# hothouse-no-branding.net
KiCad netlist of a schematic drawn in EAGLE
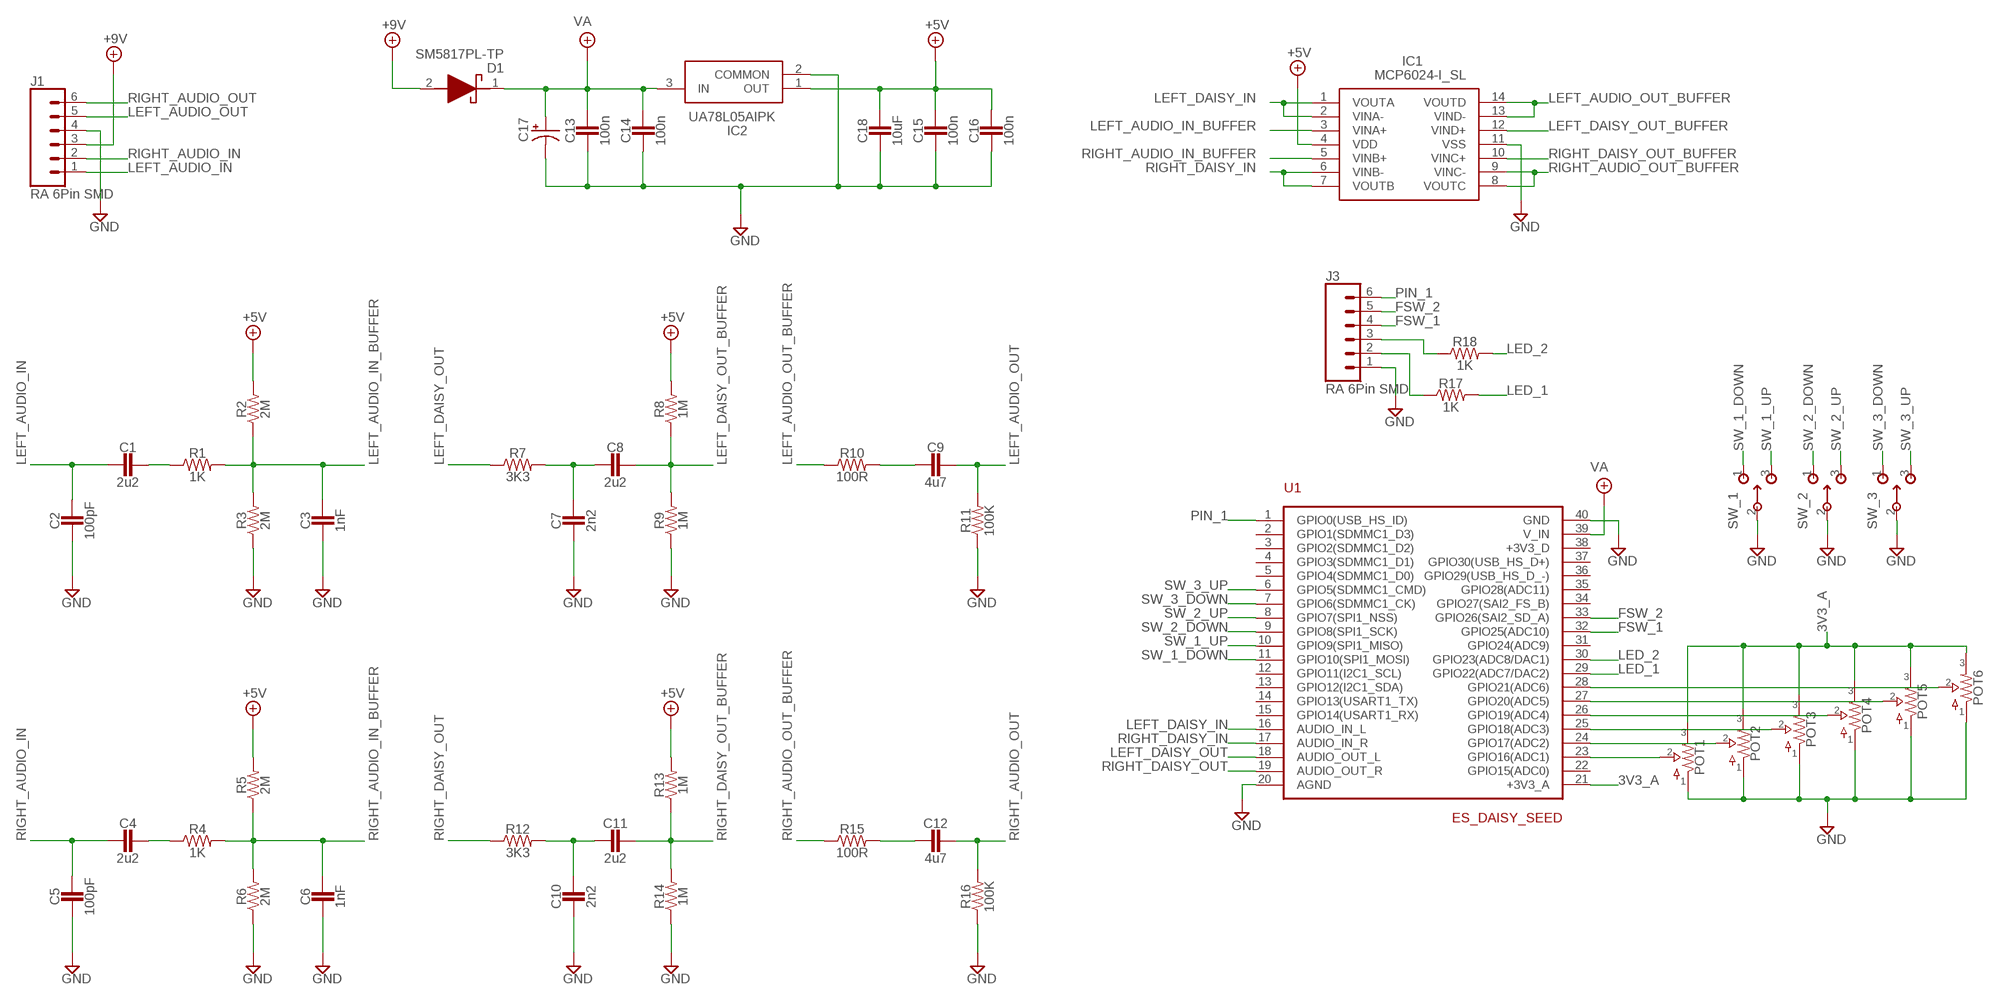
[diagram p0: schematic, sheet 1]

(export (version "E")
  (design (tool "Eeschema 10.0.6"))
  (components
    (comp (ref "C1")
      (value "2u2")
      (footprint "eagle-import:RESISTOR_C1206")
      (libsource (lib "eagle-import") (part "CAP1206"))
    )
    (comp (ref "C2")
      (value "100pF")
      (footprint "eagle-import:RESISTOR_R0603")
      (libsource (lib "eagle-import") (part "CAP0603"))
    )
    (comp (ref "C3")
      (value "1nF")
      (footprint "eagle-import:RESISTOR_R0603")
      (libsource (lib "eagle-import") (part "CAP0603"))
    )
    (comp (ref "C4")
      (value "2u2")
      (footprint "eagle-import:RESISTOR_C1206")
      (libsource (lib "eagle-import") (part "CAP1206"))
    )
    (comp (ref "C5")
      (value "100pF")
      (footprint "eagle-import:RESISTOR_R0603")
      (libsource (lib "eagle-import") (part "CAP0603"))
    )
    (comp (ref "C6")
      (value "1nF")
      (footprint "eagle-import:RESISTOR_R0603")
      (libsource (lib "eagle-import") (part "CAP0603"))
    )
    (comp (ref "C7")
      (value "2n2")
      (footprint "eagle-import:RESISTOR_R0603")
      (libsource (lib "eagle-import") (part "CAP0603"))
    )
    (comp (ref "C8")
      (value "2u2")
      (footprint "eagle-import:RESISTOR_C1206")
      (libsource (lib "eagle-import") (part "CAP1206"))
    )
    (comp (ref "C9")
      (value "4u7")
      (footprint "eagle-import:RESISTOR_C1206")
      (libsource (lib "eagle-import") (part "CAP1206"))
    )
    (comp (ref "C10")
      (value "2n2")
      (footprint "eagle-import:RESISTOR_R0603")
      (libsource (lib "eagle-import") (part "CAP0603"))
    )
    (comp (ref "C11")
      (value "2u2")
      (footprint "eagle-import:RESISTOR_C1206")
      (libsource (lib "eagle-import") (part "CAP1206"))
    )
    (comp (ref "C12")
      (value "4u7")
      (footprint "eagle-import:RESISTOR_C1206")
      (libsource (lib "eagle-import") (part "CAP1206"))
    )
    (comp (ref "C13")
      (value "100n")
      (footprint "eagle-import:RESISTOR_C0805")
      (libsource (lib "eagle-import") (part "CAP0805"))
    )
    (comp (ref "C14")
      (value "100n")
      (footprint "eagle-import:RESISTOR_C0805")
      (libsource (lib "eagle-import") (part "CAP0805"))
    )
    (comp (ref "C15")
      (value "100n")
      (footprint "eagle-import:RESISTOR_C0805")
      (libsource (lib "eagle-import") (part "CAP0805"))
    )
    (comp (ref "C16")
      (value "100n")
      (footprint "eagle-import:RESISTOR_C0805")
      (libsource (lib "eagle-import") (part "CAP0805"))
    )
    (comp (ref "C17")
      (value "0631")
      (footprint "eagle-import:063_025")
      (libsource (lib "eagle-import") (part "0631"))
    )
    (comp (ref "C18")
      (value "10uF")
      (footprint "eagle-import:RESISTOR_C0805")
      (libsource (lib "eagle-import") (part "CAP0805"))
    )
    (comp (ref "D1")
      (value "SM5817PL-TP")
      (footprint "eagle-import:SOD3716X120N")
      (fields (field (name "MOUSER_PART_NUMBER") "833-SM5817PL-TP"))
      (libsource (lib "eagle-import") (part "SM5817PL-TP"))
    )
    (comp (ref "IC1")
      (value "MCP6024-I_SL")
      (footprint "eagle-import:SOIC127P600X175-14N")
      (fields
        (field (name "MANUFACTURER_PART_NUMBER") "MCP6024-I/SL")
        (field (name "MOUSER_PART_NUMBER") "579-MCP6024-I/SL")
      )
      (libsource (lib "eagle-import") (part "MCP6024-I_SL"))
    )
    (comp (ref "IC2")
      (value "UA78L05AIPK")
      (footprint "eagle-import:PK(R-PSSO-F3)")
      (fields (field (name "MOUSER_PART_NUMBER") "595-UA78L05AIPK"))
      (libsource (lib "eagle-import") (part "UA78L05AIPK"))
    )
    (comp (ref "J1")
      (value "RA 6Pin SMD")
      (footprint "eagle-import:1X06")
      (libsource (lib "eagle-import") (part "CONN_06SILK_FEMALE_PTH"))
    )
    (comp (ref "J3")
      (value "RA 6Pin SMD")
      (footprint "eagle-import:1X06")
      (libsource (lib "eagle-import") (part "CONN_06SILK_FEMALE_PTH"))
    )
    (comp (ref "POT1")
      (value "16MM.1")
      (footprint "eagle-import:16MM_B.MOUNT")
      (libsource (lib "eagle-import") (part "16MM.1"))
    )
    (comp (ref "POT2")
      (value "16MM.1")
      (footprint "eagle-import:16MM_B.MOUNT")
      (libsource (lib "eagle-import") (part "16MM.1"))
    )
    (comp (ref "POT3")
      (value "16MM.1")
      (footprint "eagle-import:16MM_B.MOUNT")
      (libsource (lib "eagle-import") (part "16MM.1"))
    )
    (comp (ref "POT4")
      (value "16MM.1")
      (footprint "eagle-import:16MM_B.MOUNT")
      (libsource (lib "eagle-import") (part "16MM.1"))
    )
    (comp (ref "POT5")
      (value "16MM.1")
      (footprint "eagle-import:16MM_B.MOUNT")
      (libsource (lib "eagle-import") (part "16MM.1"))
    )
    (comp (ref "POT6")
      (value "16MM.1")
      (footprint "eagle-import:16MM_B.MOUNT")
      (libsource (lib "eagle-import") (part "16MM.1"))
    )
    (comp (ref "R1")
      (value "1K")
      (footprint "eagle-import:RESISTOR_R0603")
      (libsource (lib "eagle-import") (part "RESISTOR0603"))
    )
    (comp (ref "R2")
      (value "2M")
      (footprint "eagle-import:RESISTOR_R0603")
      (libsource (lib "eagle-import") (part "RESISTOR0603"))
    )
    (comp (ref "R3")
      (value "2M")
      (footprint "eagle-import:RESISTOR_R0603")
      (libsource (lib "eagle-import") (part "RESISTOR0603"))
    )
    (comp (ref "R4")
      (value "1K")
      (footprint "eagle-import:RESISTOR_R0603")
      (libsource (lib "eagle-import") (part "RESISTOR0603"))
    )
    (comp (ref "R5")
      (value "2M")
      (footprint "eagle-import:RESISTOR_R0603")
      (libsource (lib "eagle-import") (part "RESISTOR0603"))
    )
    (comp (ref "R6")
      (value "2M")
      (footprint "eagle-import:RESISTOR_R0603")
      (libsource (lib "eagle-import") (part "RESISTOR0603"))
    )
    (comp (ref "R7")
      (value "3K3")
      (footprint "eagle-import:RESISTOR_R0603")
      (libsource (lib "eagle-import") (part "RESISTOR0603"))
    )
    (comp (ref "R8")
      (value "1M")
      (footprint "eagle-import:RESISTOR_R0603")
      (libsource (lib "eagle-import") (part "RESISTOR0603"))
    )
    (comp (ref "R9")
      (value "1M")
      (footprint "eagle-import:RESISTOR_R0603")
      (libsource (lib "eagle-import") (part "RESISTOR0603"))
    )
    (comp (ref "R10")
      (value "100R")
      (footprint "eagle-import:RESISTOR_R0603")
      (libsource (lib "eagle-import") (part "RESISTOR0603"))
    )
    (comp (ref "R11")
      (value "100K")
      (footprint "eagle-import:RESISTOR_R0603")
      (libsource (lib "eagle-import") (part "RESISTOR0603"))
    )
    (comp (ref "R12")
      (value "3K3")
      (footprint "eagle-import:RESISTOR_R0603")
      (libsource (lib "eagle-import") (part "RESISTOR0603"))
    )
    (comp (ref "R13")
      (value "1M")
      (footprint "eagle-import:RESISTOR_R0603")
      (libsource (lib "eagle-import") (part "RESISTOR0603"))
    )
    (comp (ref "R14")
      (value "1M")
      (footprint "eagle-import:RESISTOR_R0603")
      (libsource (lib "eagle-import") (part "RESISTOR0603"))
    )
    (comp (ref "R15")
      (value "100R")
      (footprint "eagle-import:RESISTOR_R0603")
      (libsource (lib "eagle-import") (part "RESISTOR0603"))
    )
    (comp (ref "R16")
      (value "100K")
      (footprint "eagle-import:RESISTOR_R0603")
      (libsource (lib "eagle-import") (part "RESISTOR0603"))
    )
    (comp (ref "R17")
      (value "1K")
      (footprint "eagle-import:RESISTOR_R0603")
      (libsource (lib "eagle-import") (part "RESISTOR0603"))
    )
    (comp (ref "R18")
      (value "1K")
      (footprint "eagle-import:RESISTOR_R0603")
      (libsource (lib "eagle-import") (part "RESISTOR0603"))
    )
    (comp (ref "SW_1")
      (value "SPDT.LUGS")
      (footprint "eagle-import:SPDT.LUGS")
      (libsource (lib "eagle-import") (part "SPDT.LUGS"))
    )
    (comp (ref "SW_2")
      (value "SPDT.LUGS")
      (footprint "eagle-import:SPDT.LUGS")
      (libsource (lib "eagle-import") (part "SPDT.LUGS"))
    )
    (comp (ref "SW_3")
      (value "SPDT.LUGS")
      (footprint "eagle-import:SPDT.LUGS")
      (libsource (lib "eagle-import") (part "SPDT.LUGS"))
    )
    (comp (ref "U1")
      (value "ES_DAISY_SEED")
      (footprint "eagle-import:ES_DAISY_SEED")
      (libsource (lib "eagle-import") (part "ES_DAISY_SEED"))
    )
  )
  (nets
    (net (code "1") (name "+5V") (class "Default")
      (node (ref "C15") (pin "1") (pinfunction "1_1") (pintype "passive"))
      (node (ref "C16") (pin "1") (pinfunction "1_1") (pintype "passive"))
      (node (ref "C18") (pin "1") (pinfunction "1_1") (pintype "passive"))
      (node (ref "IC1") (pin "4") (pinfunction "VDD_4") (pintype "bidirectional"))
      (node (ref "IC2") (pin "1") (pinfunction "OUT_1") (pintype "input"))
      (node (ref "R13") (pin "2") (pinfunction "2_2") (pintype "passive"))
      (node (ref "R2") (pin "2") (pinfunction "2_2") (pintype "passive"))
      (node (ref "R5") (pin "2") (pinfunction "2_2") (pintype "passive"))
      (node (ref "R8") (pin "2") (pinfunction "2_2") (pintype "passive"))
    )
    (net (code "2") (name "+9V") (class "Default")
      (node (ref "D1") (pin "2") (pinfunction "A_2") (pintype "bidirectional"))
      (node (ref "J1") (pin "3") (pinfunction "3_3") (pintype "passive"))
    )
    (net (code "3") (name "/3V3_A") (class "Default")
      (node (ref "POT1") (pin "3") (pinfunction "3_3") (pintype "passive"))
      (node (ref "POT2") (pin "3") (pinfunction "3_3") (pintype "passive"))
      (node (ref "POT3") (pin "3") (pinfunction "3_3") (pintype "passive"))
      (node (ref "POT4") (pin "3") (pinfunction "3_3") (pintype "passive"))
      (node (ref "POT5") (pin "3") (pinfunction "3_3") (pintype "passive"))
      (node (ref "POT6") (pin "3") (pinfunction "3_3") (pintype "passive"))
      (node (ref "U1") (pin "21") (pinfunction "+3V3_A_21") (pintype "bidirectional"))
    )
    (net (code "4") (name "/FSW_1") (class "Default")
      (node (ref "J3") (pin "4") (pinfunction "4_4") (pintype "passive"))
      (node (ref "U1") (pin "32") (pinfunction "GPIO25(ADC10)_32") (pintype "bidirectional"))
    )
    (net (code "5") (name "/FSW_2") (class "Default")
      (node (ref "J3") (pin "5") (pinfunction "5_5") (pintype "passive"))
      (node (ref "U1") (pin "33") (pinfunction "GPIO26(SAI2_SD_A)_33") (pintype "bidirectional"))
    )
    (net (code "6") (name "/LED_1") (class "Default")
      (node (ref "R17") (pin "2") (pinfunction "2_2") (pintype "passive"))
      (node (ref "U1") (pin "29") (pinfunction "GPIO22(ADC7/DAC2)_29") (pintype "bidirectional"))
    )
    (net (code "7") (name "/LED_2") (class "Default")
      (node (ref "R18") (pin "2") (pinfunction "2_2") (pintype "passive"))
      (node (ref "U1") (pin "30") (pinfunction "GPIO23(ADC8/DAC1)_30") (pintype "bidirectional"))
    )
    (net (code "8") (name "/LEFT_AUDIO_IN") (class "Default")
      (node (ref "C1") (pin "2") (pinfunction "2_2") (pintype "passive"))
      (node (ref "C2") (pin "1") (pinfunction "1_1") (pintype "passive"))
      (node (ref "J1") (pin "1") (pinfunction "1_1") (pintype "passive"))
    )
    (net (code "9") (name "/LEFT_AUDIO_IN_BUFFER") (class "Default")
      (node (ref "C3") (pin "1") (pinfunction "1_1") (pintype "passive"))
      (node (ref "IC1") (pin "3") (pinfunction "VINA+_3") (pintype "bidirectional"))
      (node (ref "R1") (pin "2") (pinfunction "2_2") (pintype "passive"))
      (node (ref "R2") (pin "1") (pinfunction "1_1") (pintype "passive"))
      (node (ref "R3") (pin "2") (pinfunction "2_2") (pintype "passive"))
    )
    (net (code "10") (name "/LEFT_AUDIO_OUT") (class "Default")
      (node (ref "C9") (pin "1") (pinfunction "1_1") (pintype "passive"))
      (node (ref "J1") (pin "5") (pinfunction "5_5") (pintype "passive"))
      (node (ref "R11") (pin "2") (pinfunction "2_2") (pintype "passive"))
    )
    (net (code "11") (name "/LEFT_AUDIO_OUT_BUFFER") (class "Default")
      (node (ref "IC1") (pin "13") (pinfunction "VIND-_13") (pintype "bidirectional"))
      (node (ref "IC1") (pin "14") (pinfunction "VOUTD_14") (pintype "bidirectional"))
      (node (ref "R10") (pin "1") (pinfunction "1_1") (pintype "passive"))
    )
    (net (code "12") (name "/LEFT_DAISY_IN") (class "Default")
      (node (ref "IC1") (pin "1") (pinfunction "VOUTA_1") (pintype "bidirectional"))
      (node (ref "IC1") (pin "2") (pinfunction "VINA-_2") (pintype "bidirectional"))
      (node (ref "U1") (pin "16") (pinfunction "AUDIO_IN_L_16") (pintype "bidirectional"))
    )
    (net (code "13") (name "/LEFT_DAISY_OUT") (class "Default")
      (node (ref "R7") (pin "1") (pinfunction "1_1") (pintype "passive"))
      (node (ref "U1") (pin "18") (pinfunction "AUDIO_OUT_L_18") (pintype "bidirectional"))
    )
    (net (code "14") (name "/LEFT_DAISY_OUT_BUFFER") (class "Default")
      (node (ref "C8") (pin "1") (pinfunction "1_1") (pintype "passive"))
      (node (ref "IC1") (pin "12") (pinfunction "VIND+_12") (pintype "bidirectional"))
      (node (ref "R8") (pin "1") (pinfunction "1_1") (pintype "passive"))
      (node (ref "R9") (pin "2") (pinfunction "2_2") (pintype "passive"))
    )
    (net (code "15") (name "/PIN_1") (class "Default")
      (node (ref "J3") (pin "6") (pinfunction "6_6") (pintype "passive"))
      (node (ref "U1") (pin "1") (pinfunction "GPIO0(USB_HS_ID)_1") (pintype "bidirectional"))
    )
    (net (code "16") (name "/RIGHT_AUDIO_IN") (class "Default")
      (node (ref "C4") (pin "2") (pinfunction "2_2") (pintype "passive"))
      (node (ref "C5") (pin "1") (pinfunction "1_1") (pintype "passive"))
      (node (ref "J1") (pin "2") (pinfunction "2_2") (pintype "passive"))
    )
    (net (code "17") (name "/RIGHT_AUDIO_IN_BUFFER") (class "Default")
      (node (ref "C6") (pin "1") (pinfunction "1_1") (pintype "passive"))
      (node (ref "IC1") (pin "5") (pinfunction "VINB+_5") (pintype "bidirectional"))
      (node (ref "R4") (pin "2") (pinfunction "2_2") (pintype "passive"))
      (node (ref "R5") (pin "1") (pinfunction "1_1") (pintype "passive"))
      (node (ref "R6") (pin "2") (pinfunction "2_2") (pintype "passive"))
    )
    (net (code "18") (name "/RIGHT_AUDIO_OUT") (class "Default")
      (node (ref "C12") (pin "1") (pinfunction "1_1") (pintype "passive"))
      (node (ref "J1") (pin "6") (pinfunction "6_6") (pintype "passive"))
      (node (ref "R16") (pin "2") (pinfunction "2_2") (pintype "passive"))
    )
    (net (code "19") (name "/RIGHT_AUDIO_OUT_BUFFER") (class "Default")
      (node (ref "IC1") (pin "8") (pinfunction "VOUTC_8") (pintype "bidirectional"))
      (node (ref "IC1") (pin "9") (pinfunction "VINC-_9") (pintype "bidirectional"))
      (node (ref "R15") (pin "1") (pinfunction "1_1") (pintype "passive"))
    )
    (net (code "20") (name "/RIGHT_DAISY_IN") (class "Default")
      (node (ref "IC1") (pin "6") (pinfunction "VINB-_6") (pintype "bidirectional"))
      (node (ref "IC1") (pin "7") (pinfunction "VOUTB_7") (pintype "bidirectional"))
      (node (ref "U1") (pin "17") (pinfunction "AUDIO_IN_R_17") (pintype "bidirectional"))
    )
    (net (code "21") (name "/RIGHT_DAISY_OUT") (class "Default")
      (node (ref "R12") (pin "1") (pinfunction "1_1") (pintype "passive"))
      (node (ref "U1") (pin "19") (pinfunction "AUDIO_OUT_R_19") (pintype "bidirectional"))
    )
    (net (code "22") (name "/RIGHT_DAISY_OUT_BUFFER") (class "Default")
      (node (ref "C11") (pin "1") (pinfunction "1_1") (pintype "passive"))
      (node (ref "IC1") (pin "10") (pinfunction "VINC+_10") (pintype "bidirectional"))
      (node (ref "R13") (pin "1") (pinfunction "1_1") (pintype "passive"))
      (node (ref "R14") (pin "2") (pinfunction "2_2") (pintype "passive"))
    )
    (net (code "23") (name "/SW_1_DOWN") (class "Default")
      (node (ref "SW_1") (pin "1") (pinfunction "1_1") (pintype "passive"))
      (node (ref "U1") (pin "11") (pinfunction "GPIO10(SPI1_MOSI)_11") (pintype "bidirectional"))
    )
    (net (code "24") (name "/SW_1_UP") (class "Default")
      (node (ref "SW_1") (pin "3") (pinfunction "3_3") (pintype "passive"))
      (node (ref "U1") (pin "10") (pinfunction "GPIO9(SPI1_MISO)_10") (pintype "bidirectional"))
    )
    (net (code "25") (name "/SW_2_DOWN") (class "Default")
      (node (ref "SW_2") (pin "1") (pinfunction "1_1") (pintype "passive"))
      (node (ref "U1") (pin "9") (pinfunction "GPIO8(SPI1_SCK)_9") (pintype "bidirectional"))
    )
    (net (code "26") (name "/SW_2_UP") (class "Default")
      (node (ref "SW_2") (pin "3") (pinfunction "3_3") (pintype "passive"))
      (node (ref "U1") (pin "8") (pinfunction "GPIO7(SPI1_NSS)_8") (pintype "bidirectional"))
    )
    (net (code "27") (name "/SW_3_DOWN") (class "Default")
      (node (ref "SW_3") (pin "1") (pinfunction "1_1") (pintype "passive"))
      (node (ref "U1") (pin "7") (pinfunction "GPIO6(SDMMC1_CK)_7") (pintype "bidirectional"))
    )
    (net (code "28") (name "/SW_3_UP") (class "Default")
      (node (ref "SW_3") (pin "3") (pinfunction "3_3") (pintype "passive"))
      (node (ref "U1") (pin "6") (pinfunction "GPIO5(SDMMC1_CMD)_6") (pintype "bidirectional"))
    )
    (net (code "29") (name "GND") (class "Default")
      (node (ref "C10") (pin "2") (pinfunction "2_2") (pintype "passive"))
      (node (ref "C13") (pin "2") (pinfunction "2_2") (pintype "passive"))
      (node (ref "C14") (pin "2") (pinfunction "2_2") (pintype "passive"))
      (node (ref "C15") (pin "2") (pinfunction "2_2") (pintype "passive"))
      (node (ref "C16") (pin "2") (pinfunction "2_2") (pintype "passive"))
      (node (ref "C17") (pin "-") (pinfunction "-_-") (pintype "passive"))
      (node (ref "C18") (pin "2") (pinfunction "2_2") (pintype "passive"))
      (node (ref "C2") (pin "2") (pinfunction "2_2") (pintype "passive"))
      (node (ref "C3") (pin "2") (pinfunction "2_2") (pintype "passive"))
      (node (ref "C5") (pin "2") (pinfunction "2_2") (pintype "passive"))
      (node (ref "C6") (pin "2") (pinfunction "2_2") (pintype "passive"))
      (node (ref "C7") (pin "2") (pinfunction "2_2") (pintype "passive"))
      (node (ref "IC1") (pin "11") (pinfunction "VSS_11") (pintype "bidirectional"))
      (node (ref "IC2") (pin "2") (pinfunction "COMMON_2") (pintype "bidirectional"))
      (node (ref "J1") (pin "4") (pinfunction "4_4") (pintype "passive"))
      (node (ref "J3") (pin "1") (pinfunction "1_1") (pintype "passive"))
      (node (ref "POT1") (pin "1") (pinfunction "1_1") (pintype "passive"))
      (node (ref "POT2") (pin "1") (pinfunction "1_1") (pintype "passive"))
      (node (ref "POT3") (pin "1") (pinfunction "1_1") (pintype "passive"))
      (node (ref "POT4") (pin "1") (pinfunction "1_1") (pintype "passive"))
      (node (ref "POT5") (pin "1") (pinfunction "1_1") (pintype "passive"))
      (node (ref "POT6") (pin "1") (pinfunction "1_1") (pintype "passive"))
      (node (ref "R11") (pin "1") (pinfunction "1_1") (pintype "passive"))
      (node (ref "R14") (pin "1") (pinfunction "1_1") (pintype "passive"))
      (node (ref "R16") (pin "1") (pinfunction "1_1") (pintype "passive"))
      (node (ref "R3") (pin "1") (pinfunction "1_1") (pintype "passive"))
      (node (ref "R6") (pin "1") (pinfunction "1_1") (pintype "passive"))
      (node (ref "R9") (pin "1") (pinfunction "1_1") (pintype "passive"))
      (node (ref "SW_1") (pin "2") (pinfunction "2_2") (pintype "passive"))
      (node (ref "SW_2") (pin "2") (pinfunction "2_2") (pintype "passive"))
      (node (ref "SW_3") (pin "2") (pinfunction "2_2") (pintype "passive"))
      (node (ref "U1") (pin "20") (pinfunction "AGND_20") (pintype "bidirectional"))
      (node (ref "U1") (pin "40") (pinfunction "GND_40") (pintype "bidirectional"))
    )
    (net (code "30") (name "Net-(C1-Pad1)") (class "Default")
      (node (ref "C1") (pin "1") (pinfunction "1_1") (pintype "passive"))
      (node (ref "R1") (pin "1") (pinfunction "1_1") (pintype "passive"))
    )
    (net (code "31") (name "Net-(C4-Pad1)") (class "Default")
      (node (ref "C4") (pin "1") (pinfunction "1_1") (pintype "passive"))
      (node (ref "R4") (pin "1") (pinfunction "1_1") (pintype "passive"))
    )
    (net (code "32") (name "Net-(C7-Pad1)") (class "Default")
      (node (ref "C7") (pin "1") (pinfunction "1_1") (pintype "passive"))
      (node (ref "C8") (pin "2") (pinfunction "2_2") (pintype "passive"))
      (node (ref "R7") (pin "2") (pinfunction "2_2") (pintype "passive"))
    )
    (net (code "33") (name "Net-(C9-Pad2)") (class "Default")
      (node (ref "C9") (pin "2") (pinfunction "2_2") (pintype "passive"))
      (node (ref "R10") (pin "2") (pinfunction "2_2") (pintype "passive"))
    )
    (net (code "34") (name "Net-(C10-Pad1)") (class "Default")
      (node (ref "C10") (pin "1") (pinfunction "1_1") (pintype "passive"))
      (node (ref "C11") (pin "2") (pinfunction "2_2") (pintype "passive"))
      (node (ref "R12") (pin "2") (pinfunction "2_2") (pintype "passive"))
    )
    (net (code "35") (name "Net-(C12-Pad2)") (class "Default")
      (node (ref "C12") (pin "2") (pinfunction "2_2") (pintype "passive"))
      (node (ref "R15") (pin "2") (pinfunction "2_2") (pintype "passive"))
    )
    (net (code "36") (name "Net-(J3-Pad2)") (class "Default")
      (node (ref "J3") (pin "2") (pinfunction "2_2") (pintype "passive"))
      (node (ref "R17") (pin "1") (pinfunction "1_1") (pintype "passive"))
    )
    (net (code "37") (name "Net-(J3-Pad3)") (class "Default")
      (node (ref "J3") (pin "3") (pinfunction "3_3") (pintype "passive"))
      (node (ref "R18") (pin "1") (pinfunction "1_1") (pintype "passive"))
    )
    (net (code "38") (name "Net-(U1-GPIO16(ADC1))") (class "Default")
      (node (ref "POT1") (pin "2") (pinfunction "2_2") (pintype "passive"))
      (node (ref "U1") (pin "23") (pinfunction "GPIO16(ADC1)_23") (pintype "bidirectional"))
    )
    (net (code "39") (name "Net-(U1-GPIO17(ADC2))") (class "Default")
      (node (ref "POT2") (pin "2") (pinfunction "2_2") (pintype "passive"))
      (node (ref "U1") (pin "24") (pinfunction "GPIO17(ADC2)_24") (pintype "bidirectional"))
    )
    (net (code "40") (name "Net-(U1-GPIO18(ADC3))") (class "Default")
      (node (ref "POT3") (pin "2") (pinfunction "2_2") (pintype "passive"))
      (node (ref "U1") (pin "25") (pinfunction "GPIO18(ADC3)_25") (pintype "bidirectional"))
    )
    (net (code "41") (name "Net-(U1-GPIO19(ADC4))") (class "Default")
      (node (ref "POT4") (pin "2") (pinfunction "2_2") (pintype "passive"))
      (node (ref "U1") (pin "26") (pinfunction "GPIO19(ADC4)_26") (pintype "bidirectional"))
    )
    (net (code "42") (name "Net-(U1-GPIO20(ADC5))") (class "Default")
      (node (ref "POT5") (pin "2") (pinfunction "2_2") (pintype "passive"))
      (node (ref "U1") (pin "27") (pinfunction "GPIO20(ADC5)_27") (pintype "bidirectional"))
    )
    (net (code "43") (name "Net-(U1-GPIO21(ADC6))") (class "Default")
      (node (ref "POT6") (pin "2") (pinfunction "2_2") (pintype "passive"))
      (node (ref "U1") (pin "28") (pinfunction "GPIO21(ADC6)_28") (pintype "bidirectional"))
    )
    (net (code "44") (name "VA") (class "Default")
      (node (ref "C13") (pin "1") (pinfunction "1_1") (pintype "passive"))
      (node (ref "C14") (pin "1") (pinfunction "1_1") (pintype "passive"))
      (node (ref "C17") (pin "+") (pinfunction "+_+") (pintype "passive"))
      (node (ref "D1") (pin "1") (pinfunction "K_1") (pintype "bidirectional"))
      (node (ref "IC2") (pin "3") (pinfunction "IN_3") (pintype "output"))
      (node (ref "U1") (pin "39") (pinfunction "V_IN_39") (pintype "bidirectional"))
    )
    (net (code "45") (name "unconnected-(U1-+3V3_D-Pad38)") (class "Default")
      (node (ref "U1") (pin "38") (pinfunction "+3V3_D_38") (pintype "bidirectional"))
    )
    (net (code "46") (name "unconnected-(U1-GPIO1(SDMMC1_D3)-Pad2)") (class "Default")
      (node (ref "U1") (pin "2") (pinfunction "GPIO1(SDMMC1_D3)_2") (pintype "bidirectional"))
    )
    (net (code "47") (name "unconnected-(U1-GPIO2(SDMMC1_D2)-Pad3)") (class "Default")
      (node (ref "U1") (pin "3") (pinfunction "GPIO2(SDMMC1_D2)_3") (pintype "bidirectional"))
    )
    (net (code "48") (name "unconnected-(U1-GPIO3(SDMMC1_D1)-Pad4)") (class "Default")
      (node (ref "U1") (pin "4") (pinfunction "GPIO3(SDMMC1_D1)_4") (pintype "bidirectional"))
    )
    (net (code "49") (name "unconnected-(U1-GPIO4(SDMMC1_D0)-Pad5)") (class "Default")
      (node (ref "U1") (pin "5") (pinfunction "GPIO4(SDMMC1_D0)_5") (pintype "bidirectional"))
    )
    (net (code "50") (name "unconnected-(U1-GPIO11(I2C1_SCL)-Pad12)") (class "Default")
      (node (ref "U1") (pin "12") (pinfunction "GPIO11(I2C1_SCL)_12") (pintype "bidirectional"))
    )
    (net (code "51") (name "unconnected-(U1-GPIO12(I2C1_SDA)-Pad13)") (class "Default")
      (node (ref "U1") (pin "13") (pinfunction "GPIO12(I2C1_SDA)_13") (pintype "bidirectional"))
    )
    (net (code "52") (name "unconnected-(U1-GPIO13(USART1_TX)-Pad14)") (class "Default")
      (node (ref "U1") (pin "14") (pinfunction "GPIO13(USART1_TX)_14") (pintype "bidirectional"))
    )
    (net (code "53") (name "unconnected-(U1-GPIO14(USART1_RX)-Pad15)") (class "Default")
      (node (ref "U1") (pin "15") (pinfunction "GPIO14(USART1_RX)_15") (pintype "bidirectional"))
    )
    (net (code "54") (name "unconnected-(U1-GPIO15(ADC0)-Pad22)") (class "Default")
      (node (ref "U1") (pin "22") (pinfunction "GPIO15(ADC0)_22") (pintype "bidirectional"))
    )
    (net (code "55") (name "unconnected-(U1-GPIO24(ADC9)-Pad31)") (class "Default")
      (node (ref "U1") (pin "31") (pinfunction "GPIO24(ADC9)_31") (pintype "bidirectional"))
    )
    (net (code "56") (name "unconnected-(U1-GPIO27(SAI2_FS_B)-Pad34)") (class "Default")
      (node (ref "U1") (pin "34") (pinfunction "GPIO27(SAI2_FS_B)_34") (pintype "bidirectional"))
    )
    (net (code "57") (name "unconnected-(U1-GPIO28(ADC11)-Pad35)") (class "Default")
      (node (ref "U1") (pin "35") (pinfunction "GPIO28(ADC11)_35") (pintype "bidirectional"))
    )
    (net (code "58") (name "unconnected-(U1-GPIO29(USB_HS_D_-)-Pad36)") (class "Default")
      (node (ref "U1") (pin "36") (pinfunction "GPIO29(USB_HS_D_-)_36") (pintype "bidirectional"))
    )
    (net (code "59") (name "unconnected-(U1-GPIO30(USB_HS_D+)-Pad37)") (class "Default")
      (node (ref "U1") (pin "37") (pinfunction "GPIO30(USB_HS_D+)_37") (pintype "bidirectional"))
    )
  )
)
